# WATCHDOG.net
KiCad netlist of a schematic drawn in Altium Designer
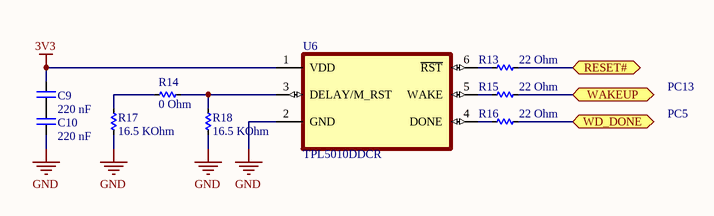
[diagram p0: WATCHDOG.SchDoc]

(export (version "E")
  (design (tool "Eeschema 10.0.6"))
  (components
    (comp (ref "C9")
      (value "220 nF")
      (footprint "CAP_C_1608X80")
      (description "CAP_Chip")
      (libsource (lib "LABLIB") (part "CAP_SMD"))
    )
    (comp (ref "C10")
      (value "220 nF")
      (footprint "CAP_C_1608X80")
      (description "CAP_Chip")
      (libsource (lib "LABLIB") (part "CAP_SMD"))
    )
    (comp (ref "R13")
      (value "22 Ohm")
      (footprint "RES_C_1608X60")
      (description "RES")
      (libsource (lib "LABLIB") (part "_RES_B_2"))
    )
    (comp (ref "R14")
      (value "0 Ohm")
      (footprint "RES_C_1608X60")
      (description "RES")
      (libsource (lib "LABLIB") (part "_RES_B_2"))
    )
    (comp (ref "R15")
      (value "22 Ohm")
      (footprint "RES_C_1608X60")
      (description "RES")
      (libsource (lib "LABLIB") (part "_RES_B_2"))
    )
    (comp (ref "R16")
      (value "22 Ohm")
      (footprint "RES_C_1608X60")
      (description "RES")
      (libsource (lib "LABLIB") (part "_RES_B_2"))
    )
    (comp (ref "R17")
      (value "16.5 KOhm")
      (footprint "RES_C_1608X60")
      (description "RES")
      (libsource (lib "LABLIB") (part "_RES_B_2"))
    )
    (comp (ref "R18")
      (value "16.5 KOhm")
      (footprint "RES_C_1608X60")
      (description "RES")
      (libsource (lib "LABLIB") (part "_RES_B_2"))
    )
    (comp (ref "U6")
      (value "TPL5010DDCR")
      (footprint "TPL5010DDCR")
      (description "OSC PROG TIMER TSOT23-6")
      (libsource (lib "IC") (part "TPL5010DDCR"))
    )
  )
  (nets
    (net (code "1") (name "/RESET#") (class "Default")
      (node (ref "R13") (pin "2") (pinfunction "2_2") (pintype "passive"))
    )
    (net (code "2") (name "/WAKEUP") (class "Default")
      (node (ref "R15") (pin "2") (pinfunction "2_2") (pintype "passive"))
    )
    (net (code "3") (name "/WD_DONE") (class "Default")
      (node (ref "R16") (pin "2") (pinfunction "2_2") (pintype "passive"))
    )
    (net (code "4") (name "3V3") (class "Default")
      (node (ref "C9") (pin "2") (pinfunction "2_2") (pintype "passive"))
      (node (ref "U6") (pin "1") (pinfunction "VDD_1") (pintype "power_in"))
    )
    (net (code "5") (name "GND") (class "Default")
      (node (ref "C10") (pin "1") (pinfunction "1_1") (pintype "passive"))
      (node (ref "R17") (pin "1") (pinfunction "1_1") (pintype "passive"))
      (node (ref "R18") (pin "1") (pinfunction "1_1") (pintype "passive"))
      (node (ref "U6") (pin "2") (pinfunction "GND_2") (pintype "power_in"))
    )
    (net (code "6") (name "Net-(C10-Pad2)") (class "Default")
      (node (ref "C10") (pin "2") (pinfunction "2_2") (pintype "passive"))
      (node (ref "C9") (pin "1") (pinfunction "1_1") (pintype "passive"))
    )
    (net (code "7") (name "Net-(R14-Pad1)") (class "Default")
      (node (ref "R14") (pin "1") (pinfunction "1_1") (pintype "passive"))
      (node (ref "R17") (pin "2") (pinfunction "2_2") (pintype "passive"))
    )
    (net (code "8") (name "Net-(U6-DELAY{slash}M_RST)") (class "Default")
      (node (ref "R14") (pin "2") (pinfunction "2_2") (pintype "passive"))
      (node (ref "R18") (pin "2") (pinfunction "2_2") (pintype "passive"))
      (node (ref "U6") (pin "3") (pinfunction "DELAY/M_RST_3") (pintype "bidirectional"))
    )
    (net (code "9") (name "Net-(U6-DONE)") (class "Default")
      (node (ref "R16") (pin "1") (pinfunction "1_1") (pintype "passive"))
      (node (ref "U6") (pin "4") (pinfunction "DONE_4") (pintype "bidirectional"))
    )
    (net (code "10") (name "Net-(U6-WAKE)") (class "Default")
      (node (ref "R15") (pin "1") (pinfunction "1_1") (pintype "passive"))
      (node (ref "U6") (pin "5") (pinfunction "WAKE_5") (pintype "bidirectional"))
    )
    (net (code "11") (name "Net-(U6-~{RST})") (class "Default")
      (node (ref "R13") (pin "1") (pinfunction "1_1") (pintype "passive"))
      (node (ref "U6") (pin "6") (pinfunction "~{RST}_6") (pintype "bidirectional"))
    )
  )
)
